# gnat.net
KiCad netlist of a schematic drawn in EAGLE
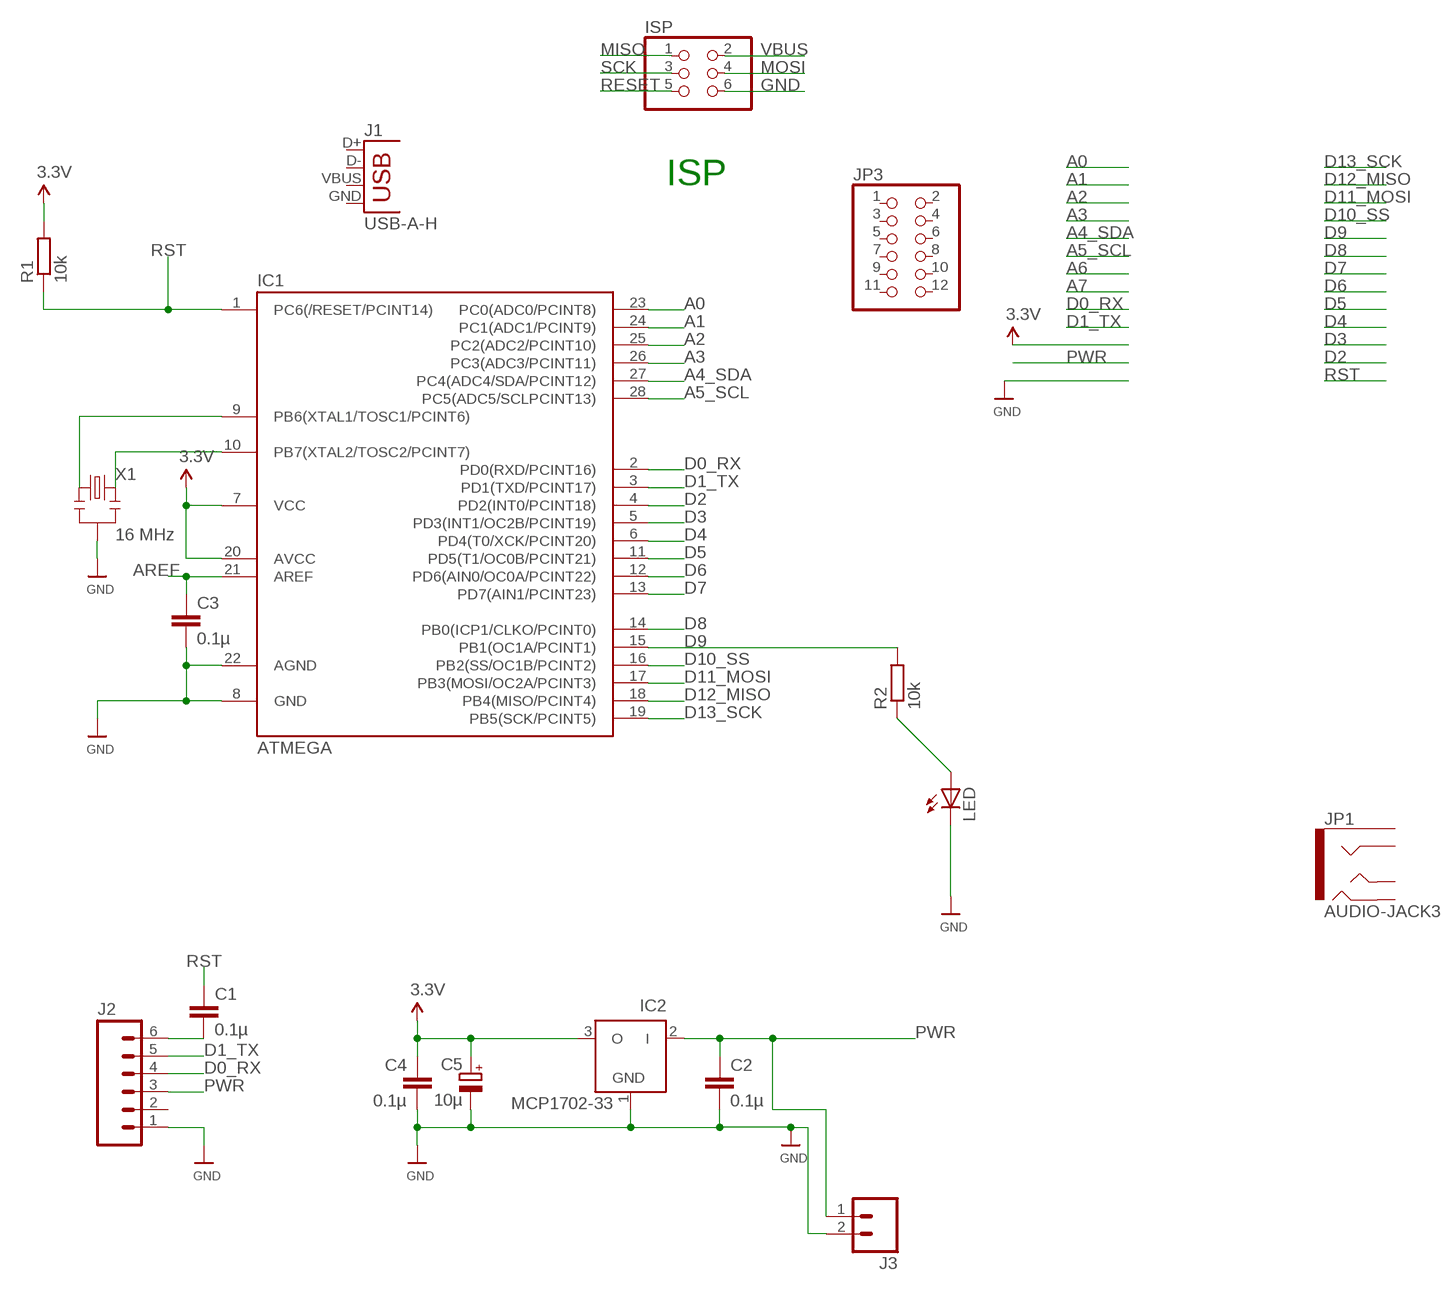
[diagram p0: schematic, sheet 1]

(export (version "E")
  (design (tool "Eeschema 10.0.6"))
  (components
    (comp (ref "C1")
      (value "0.1µ")
      (footprint "eagle-import:C025-024X044")
      (libsource (lib "eagle-import") (part "C-EU025-024X044"))
    )
    (comp (ref "C2")
      (value "0.1µ")
      (footprint "eagle-import:C025-024X044")
      (libsource (lib "eagle-import") (part "C-EU025-024X044"))
    )
    (comp (ref "C3")
      (value "0.1µ")
      (footprint "eagle-import:C025-024X044")
      (libsource (lib "eagle-import") (part "C-EU025-024X044"))
    )
    (comp (ref "C4")
      (value "0.1µ")
      (footprint "eagle-import:C025-024X044")
      (libsource (lib "eagle-import") (part "C-EU025-024X044"))
    )
    (comp (ref "C5")
      (value "10µ")
      (footprint "eagle-import:E1,8-4")
      (libsource (lib "eagle-import") (part "CPOL-EUE1.8-4"))
    )
    (comp (ref "IC1")
      (value "ATMEGA")
      (footprint "eagle-import:DIL28-3")
      (libsource (lib "eagle-import") (part "ATMEGA48/88/168-PU"))
    )
    (comp (ref "IC2")
      (value "MCP1702-33")
      (footprint "eagle-import:TO92")
      (libsource (lib "eagle-import") (part "MCP1702Z"))
    )
    (comp (ref "ISP")
      (value "PINHD-2X3")
      (footprint "eagle-import:2X03")
      (libsource (lib "eagle-import") (part "PINHD-2X3"))
    )
    (comp (ref "J1")
      (value "USB-A-H")
      (footprint "eagle-import:USB-A-H")
      (libsource (lib "eagle-import") (part "USB-A-H"))
    )
    (comp (ref "J2")
      (value "M06SILK_FEMALE_PTH")
      (footprint "eagle-import:1X06")
      (libsource (lib "eagle-import") (part "M06SILK_FEMALE_PTH"))
    )
    (comp (ref "J3")
      (value "M02PTH")
      (footprint "eagle-import:1X02")
      (libsource (lib "eagle-import") (part "M02PTH"))
    )
    (comp (ref "JP1")
      (value "AUDIO-JACK3")
      (footprint "eagle-import:AUDIO-JACK-TRRS-SMD")
      (libsource (lib "eagle-import") (part "AUDIO-JACK3"))
    )
    (comp (ref "JP3")
      (value "PINHD-2X6")
      (footprint "eagle-import:2X06")
      (libsource (lib "eagle-import") (part "PINHD-2X6"))
    )
    (comp (ref "LED")
      (value "LED3MM")
      (footprint "eagle-import:LED3MM")
      (libsource (lib "eagle-import") (part "LED3MM"))
    )
    (comp (ref "R1")
      (value "10k")
      (footprint "eagle-import:0204_7")
      (libsource (lib "eagle-import") (part "R-EU_0204/7"))
    )
    (comp (ref "R2")
      (value "10k")
      (footprint "eagle-import:0204_7")
      (libsource (lib "eagle-import") (part "R-EU_0204/7"))
    )
    (comp (ref "X1")
      (value "16 MHz")
      (footprint "eagle-import:RESONATOR-PTH")
      (libsource (lib "eagle-import") (part "RESONATORPTH"))
    )
  )
  (nets
    (net (code "1") (name "/A0") (class "Default")
      (node (ref "IC1") (pin "23") (pinfunction "PC0(ADC0/PCINT8)_23") (pintype "bidirectional"))
    )
    (net (code "2") (name "/A1") (class "Default")
      (node (ref "IC1") (pin "24") (pinfunction "PC1(ADC1/PCINT9)_24") (pintype "bidirectional"))
    )
    (net (code "3") (name "/A2") (class "Default")
      (node (ref "IC1") (pin "25") (pinfunction "PC2(ADC2/PCINT10)_25") (pintype "bidirectional"))
    )
    (net (code "4") (name "/A3") (class "Default")
      (node (ref "IC1") (pin "26") (pinfunction "PC3(ADC3/PCINT11)_26") (pintype "bidirectional"))
    )
    (net (code "5") (name "/A4_SDA") (class "Default")
      (node (ref "IC1") (pin "27") (pinfunction "PC4(ADC4/SDA/PCINT12)_27") (pintype "bidirectional"))
    )
    (net (code "6") (name "/A5_SCL") (class "Default")
      (node (ref "IC1") (pin "28") (pinfunction "PC5(ADC5/SCLPCINT13)_28") (pintype "bidirectional"))
    )
    (net (code "9") (name "/AREF") (class "Default")
      (node (ref "C3") (pin "1") (pinfunction "1_1") (pintype "passive"))
      (node (ref "IC1") (pin "21") (pinfunction "AREF_21") (pintype "passive"))
    )
    (net (code "10") (name "/D0_RX") (class "Default")
      (node (ref "IC1") (pin "2") (pinfunction "PD0(RXD/PCINT16)_2") (pintype "bidirectional"))
      (node (ref "J2") (pin "4") (pinfunction "4_4") (pintype "passive"))
    )
    (net (code "11") (name "/D1_TX") (class "Default")
      (node (ref "IC1") (pin "3") (pinfunction "PD1(TXD/PCINT17)_3") (pintype "bidirectional"))
      (node (ref "J2") (pin "5") (pinfunction "5_5") (pintype "passive"))
    )
    (net (code "12") (name "/D2") (class "Default")
      (node (ref "IC1") (pin "4") (pinfunction "PD2(INT0/PCINT18)_4") (pintype "bidirectional"))
    )
    (net (code "13") (name "/D3") (class "Default")
      (node (ref "IC1") (pin "5") (pinfunction "PD3(INT1/OC2B/PCINT19)_5") (pintype "bidirectional"))
    )
    (net (code "14") (name "/D4") (class "Default")
      (node (ref "IC1") (pin "6") (pinfunction "PD4(T0/XCK/PCINT20)_6") (pintype "bidirectional"))
    )
    (net (code "15") (name "/D5") (class "Default")
      (node (ref "IC1") (pin "11") (pinfunction "PD5(T1/OC0B/PCINT21)_11") (pintype "bidirectional"))
    )
    (net (code "16") (name "/D6") (class "Default")
      (node (ref "IC1") (pin "12") (pinfunction "PD6(AIN0/OC0A/PCINT22)_12") (pintype "bidirectional"))
    )
    (net (code "17") (name "/D7") (class "Default")
      (node (ref "IC1") (pin "13") (pinfunction "PD7(AIN1/PCINT23)_13") (pintype "bidirectional"))
    )
    (net (code "18") (name "/D8") (class "Default")
      (node (ref "IC1") (pin "14") (pinfunction "PB0(ICP1/CLKO/PCINT0)_14") (pintype "bidirectional"))
    )
    (net (code "19") (name "/D9") (class "Default")
      (node (ref "IC1") (pin "15") (pinfunction "PB1(OC1A/PCINT1)_15") (pintype "bidirectional"))
      (node (ref "R2") (pin "2") (pinfunction "2_2") (pintype "passive"))
    )
    (net (code "20") (name "/D10_SS") (class "Default")
      (node (ref "IC1") (pin "16") (pinfunction "PB2(SS/OC1B/PCINT2)_16") (pintype "bidirectional"))
    )
    (net (code "21") (name "/D11_MOSI") (class "Default")
      (node (ref "IC1") (pin "17") (pinfunction "PB3(MOSI/OC2A/PCINT3)_17") (pintype "bidirectional"))
    )
    (net (code "22") (name "/D12_MISO") (class "Default")
      (node (ref "IC1") (pin "18") (pinfunction "PB4(MISO/PCINT4)_18") (pintype "bidirectional"))
    )
    (net (code "23") (name "/D13_SCK") (class "Default")
      (node (ref "IC1") (pin "19") (pinfunction "PB5(SCK/PCINT5)_19") (pintype "bidirectional"))
    )
    (net (code "24") (name "/MISO") (class "Default")
      (node (ref "ISP") (pin "1") (pinfunction "1_1") (pintype "passive"))
    )
    (net (code "25") (name "/MOSI") (class "Default")
      (node (ref "ISP") (pin "4") (pinfunction "4_4") (pintype "passive"))
    )
    (net (code "26") (name "/PWR") (class "Default")
      (node (ref "C2") (pin "1") (pinfunction "1_1") (pintype "passive"))
      (node (ref "IC2") (pin "2") (pinfunction "I_2") (pintype "input"))
      (node (ref "J2") (pin "3") (pinfunction "3_3") (pintype "passive"))
      (node (ref "J3") (pin "1") (pinfunction "1_1") (pintype "passive"))
    )
    (net (code "27") (name "/RESET") (class "Default")
      (node (ref "ISP") (pin "5") (pinfunction "5_5") (pintype "passive"))
    )
    (net (code "28") (name "/RST") (class "Default")
      (node (ref "C1") (pin "1") (pinfunction "1_1") (pintype "passive"))
      (node (ref "IC1") (pin "1") (pinfunction "PC6(/RESET/PCINT14)_1") (pintype "bidirectional"))
      (node (ref "R1") (pin "1") (pinfunction "1_1") (pintype "passive"))
    )
    (net (code "29") (name "/SCK") (class "Default")
      (node (ref "ISP") (pin "3") (pinfunction "3_3") (pintype "passive"))
    )
    (net (code "30") (name "/VBUS") (class "Default")
      (node (ref "ISP") (pin "2") (pinfunction "2_2") (pintype "passive"))
    )
    (net (code "31") (name "3.3V") (class "Default")
      (node (ref "C4") (pin "1") (pinfunction "1_1") (pintype "passive"))
      (node (ref "C5") (pin "+") (pinfunction "+_+") (pintype "passive"))
      (node (ref "IC1") (pin "20") (pinfunction "AVCC_20") (pintype "passive"))
      (node (ref "IC1") (pin "7") (pinfunction "VCC_7") (pintype "power_in"))
      (node (ref "IC2") (pin "3") (pinfunction "O_3") (pintype "input"))
      (node (ref "R1") (pin "2") (pinfunction "2_2") (pintype "passive"))
    )
    (net (code "32") (name "GND") (class "Default")
      (node (ref "C2") (pin "2") (pinfunction "2_2") (pintype "passive"))
      (node (ref "C3") (pin "2") (pinfunction "2_2") (pintype "passive"))
      (node (ref "C4") (pin "2") (pinfunction "2_2") (pintype "passive"))
      (node (ref "C5") (pin "-") (pinfunction "-_-") (pintype "passive"))
      (node (ref "IC1") (pin "22") (pinfunction "AGND_22") (pintype "power_in"))
      (node (ref "IC1") (pin "8") (pinfunction "GND_8") (pintype "power_in"))
      (node (ref "IC2") (pin "1") (pinfunction "GND_1") (pintype "power_in"))
      (node (ref "ISP") (pin "6") (pinfunction "6_6") (pintype "passive"))
      (node (ref "J2") (pin "1") (pinfunction "1_1") (pintype "passive"))
      (node (ref "J3") (pin "2") (pinfunction "2_2") (pintype "passive"))
      (node (ref "LED") (pin "K") (pinfunction "C_K") (pintype "passive"))
      (node (ref "X1") (pin "2") (pinfunction "2_2") (pintype "passive"))
    )
    (net (code "33") (name "Net-(C1-Pad2)") (class "Default")
      (node (ref "C1") (pin "2") (pinfunction "2_2") (pintype "passive"))
      (node (ref "J2") (pin "6") (pinfunction "6_6") (pintype "passive"))
    )
    (net (code "34") (name "Net-(IC1-PB6(XTAL1{slash}TOSC1{slash}PCINT6))") (class "Default")
      (node (ref "IC1") (pin "9") (pinfunction "PB6(XTAL1/TOSC1/PCINT6)_9") (pintype "bidirectional"))
      (node (ref "X1") (pin "1") (pinfunction "1_1") (pintype "passive"))
    )
    (net (code "35") (name "Net-(IC1-PB7(XTAL2{slash}TOSC2{slash}PCINT7))") (class "Default")
      (node (ref "IC1") (pin "10") (pinfunction "PB7(XTAL2/TOSC2/PCINT7)_10") (pintype "bidirectional"))
      (node (ref "X1") (pin "3") (pinfunction "3_3") (pintype "passive"))
    )
    (net (code "36") (name "Net-(LED-PadA)") (class "Default")
      (node (ref "LED") (pin "A") (pinfunction "A_A") (pintype "passive"))
      (node (ref "R2") (pin "1") (pinfunction "1_1") (pintype "passive"))
    )
    (net (code "37") (name "unconnected-(J1-PadD+)") (class "Default")
      (node (ref "J1") (pin "D+") (pinfunction "D+_D+") (pintype "bidirectional"))
    )
    (net (code "38") (name "unconnected-(J1-PadD-)") (class "Default")
      (node (ref "J1") (pin "D-") (pinfunction "D-_D-") (pintype "bidirectional"))
    )
    (net (code "39") (name "unconnected-(J1-PadGND)") (class "Default")
      (node (ref "J1") (pin "GND") (pinfunction "GND_GND") (pintype "bidirectional"))
    )
    (net (code "40") (name "unconnected-(J1-PadVBUS)") (class "Default")
      (node (ref "J1") (pin "VBUS") (pinfunction "VBUS_VBUS") (pintype "bidirectional"))
    )
    (net (code "41") (name "unconnected-(J2-Pad2)") (class "Default")
      (node (ref "J2") (pin "2") (pinfunction "2_2") (pintype "passive"))
    )
    (net (code "42") (name "unconnected-(JP1-PadEARTH)") (class "Default")
      (node (ref "JP1") (pin "EARTH") (pinfunction "EARTH_EARTH") (pintype "bidirectional"))
    )
    (net (code "43") (name "unconnected-(JP1-PadRING1)") (class "Default")
      (node (ref "JP1") (pin "RING1") (pinfunction "RING1_RING1") (pintype "bidirectional"))
    )
    (net (code "44") (name "unconnected-(JP1-PadRING2)") (class "Default")
      (node (ref "JP1") (pin "RING2") (pinfunction "RING2_RING2") (pintype "bidirectional"))
    )
    (net (code "45") (name "unconnected-(JP1-PadTIP)") (class "Default")
      (node (ref "JP1") (pin "TIP") (pinfunction "TIP_TIP") (pintype "bidirectional"))
    )
    (net (code "46") (name "unconnected-(JP3-Pad1)") (class "Default")
      (node (ref "JP3") (pin "1") (pinfunction "1_1") (pintype "passive"))
    )
    (net (code "47") (name "unconnected-(JP3-Pad2)") (class "Default")
      (node (ref "JP3") (pin "2") (pinfunction "2_2") (pintype "passive"))
    )
    (net (code "48") (name "unconnected-(JP3-Pad3)") (class "Default")
      (node (ref "JP3") (pin "3") (pinfunction "3_3") (pintype "passive"))
    )
    (net (code "49") (name "unconnected-(JP3-Pad4)") (class "Default")
      (node (ref "JP3") (pin "4") (pinfunction "4_4") (pintype "passive"))
    )
    (net (code "50") (name "unconnected-(JP3-Pad5)") (class "Default")
      (node (ref "JP3") (pin "5") (pinfunction "5_5") (pintype "passive"))
    )
    (net (code "51") (name "unconnected-(JP3-Pad6)") (class "Default")
      (node (ref "JP3") (pin "6") (pinfunction "6_6") (pintype "passive"))
    )
    (net (code "52") (name "unconnected-(JP3-Pad7)") (class "Default")
      (node (ref "JP3") (pin "7") (pinfunction "7_7") (pintype "passive"))
    )
    (net (code "53") (name "unconnected-(JP3-Pad8)") (class "Default")
      (node (ref "JP3") (pin "8") (pinfunction "8_8") (pintype "passive"))
    )
    (net (code "54") (name "unconnected-(JP3-Pad9)") (class "Default")
      (node (ref "JP3") (pin "9") (pinfunction "9_9") (pintype "passive"))
    )
    (net (code "55") (name "unconnected-(JP3-Pad10)") (class "Default")
      (node (ref "JP3") (pin "10") (pinfunction "10_10") (pintype "passive"))
    )
    (net (code "56") (name "unconnected-(JP3-Pad11)") (class "Default")
      (node (ref "JP3") (pin "11") (pinfunction "11_11") (pintype "passive"))
    )
    (net (code "57") (name "unconnected-(JP3-Pad12)") (class "Default")
      (node (ref "JP3") (pin "12") (pinfunction "12_12") (pintype "passive"))
    )
  )
)
